# MCU_Module_V1.net
KiCad netlist of a schematic drawn in EAGLE
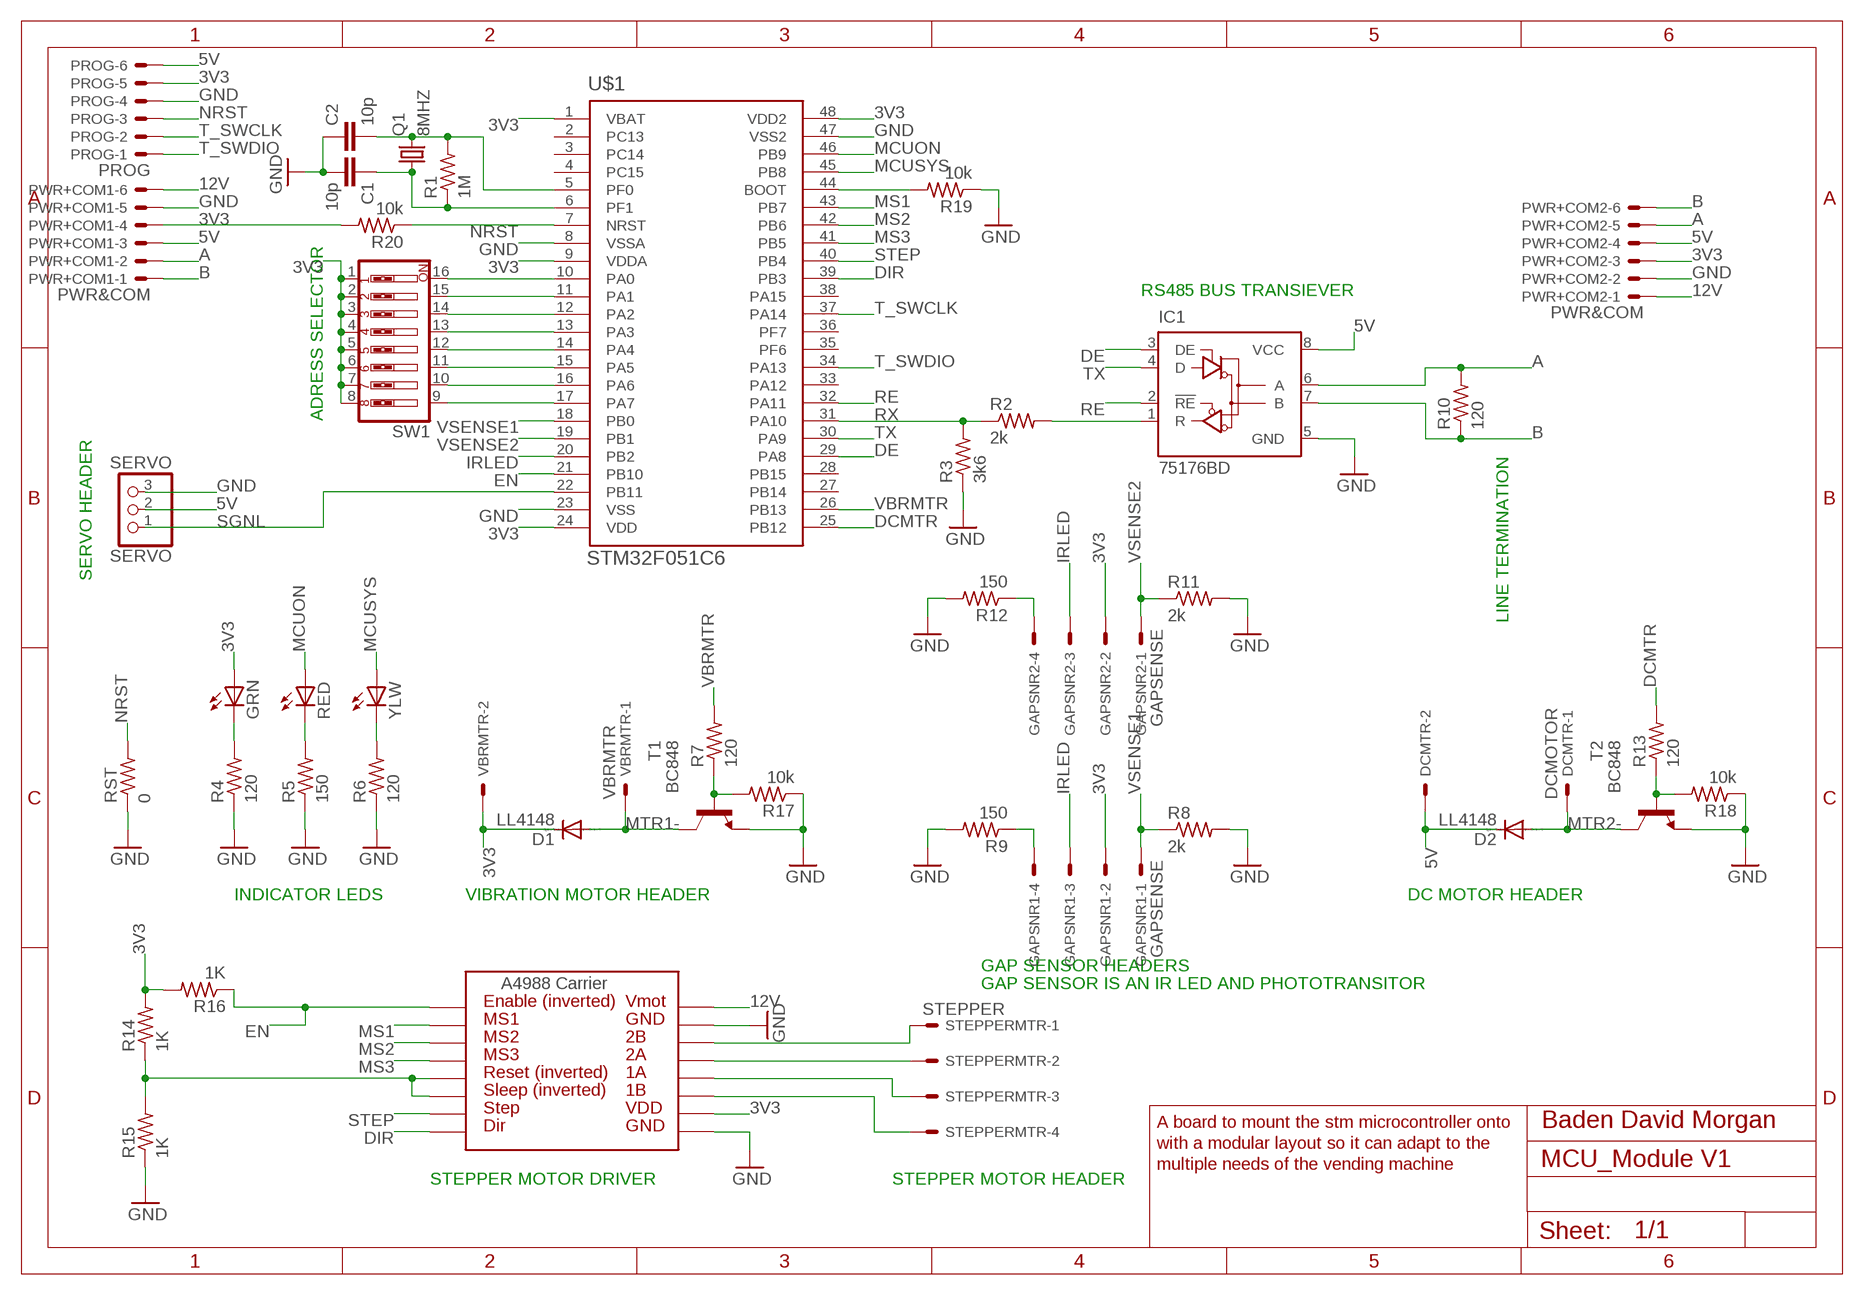
[diagram p0: schematic, sheet 1]

(export (version "E")
  (design (tool "Eeschema 10.0.6"))
  (components
    (comp (ref "C1")
      (value "10p")
      (footprint "eagle-import:C0805")
      (libsource (lib "eagle-import") (part "C-EUC0805"))
    )
    (comp (ref "C2")
      (value "10p")
      (footprint "eagle-import:C0805")
      (libsource (lib "eagle-import") (part "C-EUC0805"))
    )
    (comp (ref "D1")
      (value "LL4148")
      (footprint "eagle-import:SOD80C")
      (libsource (lib "eagle-import") (part "PMLL4150"))
    )
    (comp (ref "D2")
      (value "LL4148")
      (footprint "eagle-import:SOD80C")
      (libsource (lib "eagle-import") (part "PMLL4150"))
    )
    (comp (ref "DCMTR")
      (value "DCMOTOR")
      (footprint "eagle-import:6410-02")
      (libsource (lib "eagle-import") (part "22-?-0227-2021"))
    )
    (comp (ref "GAPSNR1")
      (value "GAPSENSE")
      (footprint "eagle-import:6410-04")
      (libsource (lib "eagle-import") (part "22-?-0427-2041"))
    )
    (comp (ref "GAPSNR2")
      (value "GAPSENSE")
      (footprint "eagle-import:6410-04")
      (libsource (lib "eagle-import") (part "22-?-0427-2041"))
    )
    (comp (ref "GRN")
      (value "LEDSML1206")
      (footprint "eagle-import:SML1206")
      (libsource (lib "eagle-import") (part "LEDSML1206"))
    )
    (comp (ref "IC1")
      (value "75176BD")
      (footprint "eagle-import:D_R-PDSO-G8")
      (libsource (lib "eagle-import") (part "75176AD"))
    )
    (comp (ref "PROG")
      (value "PROG")
      (footprint "eagle-import:6410-06")
      (libsource (lib "eagle-import") (part "22-?-0627-2061"))
    )
    (comp (ref "PWR+COM1")
      (value "PWR&COM")
      (footprint "eagle-import:7395-06")
      (libsource (lib "eagle-import") (part "22-?-0605-7068"))
    )
    (comp (ref "PWR+COM2")
      (value "PWR&COM")
      (footprint "eagle-import:7395-06")
      (libsource (lib "eagle-import") (part "22-?-0605-7068"))
    )
    (comp (ref "Q1")
      (value "8MHZ")
      (footprint "eagle-import:SM49")
      (libsource (lib "eagle-import") (part "CRYSTALSM49"))
    )
    (comp (ref "R1")
      (value "1M")
      (footprint "eagle-import:R0805")
      (libsource (lib "eagle-import") (part "R-US_R0805"))
    )
    (comp (ref "R2")
      (value "2k")
      (footprint "eagle-import:R0805")
      (libsource (lib "eagle-import") (part "resistor_R-US_R0805"))
    )
    (comp (ref "R3")
      (value "3k6")
      (footprint "eagle-import:R0805")
      (libsource (lib "eagle-import") (part "resistor_R-US_R0805"))
    )
    (comp (ref "R4")
      (value "120")
      (footprint "eagle-import:R0805")
      (libsource (lib "eagle-import") (part "R-US_R0805"))
    )
    (comp (ref "R5")
      (value "150")
      (footprint "eagle-import:R0805")
      (libsource (lib "eagle-import") (part "R-US_R0805"))
    )
    (comp (ref "R6")
      (value "120")
      (footprint "eagle-import:R0805")
      (libsource (lib "eagle-import") (part "R-US_R0805"))
    )
    (comp (ref "R7")
      (value "120")
      (footprint "eagle-import:R0805")
      (libsource (lib "eagle-import") (part "R-US_R0805"))
    )
    (comp (ref "R8")
      (value "2k")
      (footprint "eagle-import:R0805")
      (libsource (lib "eagle-import") (part "resistor_R-US_R0805"))
    )
    (comp (ref "R9")
      (value "150")
      (footprint "eagle-import:R0805")
      (libsource (lib "eagle-import") (part "R-US_R0805"))
    )
    (comp (ref "R10")
      (value "120")
      (footprint "eagle-import:R0805")
      (libsource (lib "eagle-import") (part "resistor_R-US_R0805"))
    )
    (comp (ref "R11")
      (value "2k")
      (footprint "eagle-import:R0805")
      (libsource (lib "eagle-import") (part "resistor_R-US_R0805"))
    )
    (comp (ref "R12")
      (value "150")
      (footprint "eagle-import:R0805")
      (libsource (lib "eagle-import") (part "R-US_R0805"))
    )
    (comp (ref "R13")
      (value "120")
      (footprint "eagle-import:R0805")
      (libsource (lib "eagle-import") (part "R-US_R0805"))
    )
    (comp (ref "R14")
      (value "1K")
      (footprint "eagle-import:R0805")
      (libsource (lib "eagle-import") (part "R-US_R0805"))
    )
    (comp (ref "R15")
      (value "1K")
      (footprint "eagle-import:R0805")
      (libsource (lib "eagle-import") (part "R-US_R0805"))
    )
    (comp (ref "R16")
      (value "1K")
      (footprint "eagle-import:R0805")
      (libsource (lib "eagle-import") (part "R-US_R0805"))
    )
    (comp (ref "R17")
      (value "10k")
      (footprint "eagle-import:R0805")
      (libsource (lib "eagle-import") (part "R-US_R0805"))
    )
    (comp (ref "R18")
      (value "10k")
      (footprint "eagle-import:R0805")
      (libsource (lib "eagle-import") (part "R-US_R0805"))
    )
    (comp (ref "R19")
      (value "10k")
      (footprint "eagle-import:R0805")
      (libsource (lib "eagle-import") (part "R-US_R0805"))
    )
    (comp (ref "R20")
      (value "10k")
      (footprint "eagle-import:R0805")
      (libsource (lib "eagle-import") (part "R-US_R0805"))
    )
    (comp (ref "RED")
      (value "LEDSML1206")
      (footprint "eagle-import:SML1206")
      (libsource (lib "eagle-import") (part "LEDSML1206"))
    )
    (comp (ref "RST")
      (value "0")
      (footprint "eagle-import:R0805")
      (libsource (lib "eagle-import") (part "R-US_R0805"))
    )
    (comp (ref "SERVO")
      (value "SERVO")
      (footprint "eagle-import:1X03")
      (libsource (lib "eagle-import") (part "PINHD-1X3"))
    )
    (comp (ref "STEPPERMTR")
      (value "STEPPER")
      (footprint "eagle-import:6410-04")
      (libsource (lib "eagle-import") (part "22-?-0427-2041"))
    )
    (comp (ref "SW1")
      (value "SW_DIP-8")
      (footprint "eagle-import:EDG-08")
      (libsource (lib "eagle-import") (part "SW_DIP-8"))
    )
    (comp (ref "T1")
      (value "BC848")
      (footprint "eagle-import:SOT23")
      (libsource (lib "eagle-import") (part "BC848"))
    )
    (comp (ref "T2")
      (value "BC848")
      (footprint "eagle-import:SOT23")
      (libsource (lib "eagle-import") (part "BC848"))
    )
    (comp (ref "U$1")
      (value "STM32F051C6")
      (footprint "eagle-import:QFP50P900X900X160-48N")
      (libsource (lib "eagle-import") (part "STM32F051C6"))
    )
    (comp (ref "U$2")
      (value "A4983CARRIER")
      (footprint "eagle-import:A4988BREAKOUT")
      (libsource (lib "eagle-import") (part "A4983CARRIER"))
    )
    (comp (ref "VBRMTR")
      (value "VBRMTR")
      (footprint "eagle-import:6410-02")
      (libsource (lib "eagle-import") (part "22-?-0227-2021"))
    )
    (comp (ref "YLW")
      (value "LEDSML1206")
      (footprint "eagle-import:SML1206")
      (libsource (lib "eagle-import") (part "LEDSML1206"))
    )
  )
  (nets
    (net (code "1") (name "/3V3") (class "Default")
      (node (ref "D1") (pin "C") (pinfunction "C_C") (pintype "passive"))
      (node (ref "GAPSNR1") (pin "2") (pinfunction "S_2") (pintype "passive"))
      (node (ref "GAPSNR2") (pin "2") (pinfunction "S_2") (pintype "passive"))
      (node (ref "GRN") (pin "A") (pinfunction "A_A") (pintype "passive"))
      (node (ref "PROG") (pin "5") (pinfunction "S_5") (pintype "passive"))
      (node (ref "PWR+COM1") (pin "4") (pinfunction "S_4") (pintype "passive"))
      (node (ref "PWR+COM2") (pin "3") (pinfunction "S_3") (pintype "passive"))
      (node (ref "R14") (pin "2") (pinfunction "2_2") (pintype "passive"))
      (node (ref "R16") (pin "2") (pinfunction "2_2") (pintype "passive"))
      (node (ref "R20") (pin "2") (pinfunction "2_2") (pintype "passive"))
      (node (ref "SW1") (pin "1") (pinfunction "1_1") (pintype "passive"))
      (node (ref "SW1") (pin "2") (pinfunction "2_2") (pintype "passive"))
      (node (ref "SW1") (pin "3") (pinfunction "3_3") (pintype "passive"))
      (node (ref "SW1") (pin "4") (pinfunction "4_4") (pintype "passive"))
      (node (ref "SW1") (pin "5") (pinfunction "5_5") (pintype "passive"))
      (node (ref "SW1") (pin "6") (pinfunction "6_6") (pintype "passive"))
      (node (ref "SW1") (pin "7") (pinfunction "7_7") (pintype "passive"))
      (node (ref "SW1") (pin "8") (pinfunction "8_8") (pintype "passive"))
      (node (ref "U$1") (pin "1") (pinfunction "VBAT_1") (pintype "bidirectional"))
      (node (ref "U$1") (pin "24") (pinfunction "VDD_24") (pintype "bidirectional"))
      (node (ref "U$1") (pin "48") (pinfunction "VDD2_48") (pintype "bidirectional"))
      (node (ref "U$1") (pin "9") (pinfunction "VDDA_9") (pintype "bidirectional"))
      (node (ref "U$2") (pin "VDD") (pinfunction "VDD_VDD") (pintype "power_in"))
      (node (ref "VBRMTR") (pin "2") (pinfunction "S_2") (pintype "passive"))
    )
    (net (code "2") (name "/5V") (class "Default")
      (node (ref "D2") (pin "C") (pinfunction "C_C") (pintype "passive"))
      (node (ref "DCMTR") (pin "2") (pinfunction "S_2") (pintype "passive"))
      (node (ref "IC1") (pin "8") (pinfunction "VCC_8") (pintype "power_in"))
      (node (ref "PROG") (pin "6") (pinfunction "S_6") (pintype "passive"))
      (node (ref "PWR+COM1") (pin "3") (pinfunction "S_3") (pintype "passive"))
      (node (ref "PWR+COM2") (pin "4") (pinfunction "S_4") (pintype "passive"))
      (node (ref "SERVO") (pin "2") (pinfunction "2_2") (pintype "passive"))
    )
    (net (code "3") (name "/12V") (class "Default")
      (node (ref "PWR+COM1") (pin "6") (pinfunction "S_6") (pintype "passive"))
      (node (ref "PWR+COM2") (pin "1") (pinfunction "S_1") (pintype "passive"))
      (node (ref "U$2") (pin "VMOT") (pinfunction "VMOT_VMOT") (pintype "power_in"))
    )
    (net (code "4") (name "/A") (class "Default")
      (node (ref "IC1") (pin "6") (pinfunction "A_6") (pintype "output"))
      (node (ref "PWR+COM1") (pin "2") (pinfunction "S_2") (pintype "passive"))
      (node (ref "PWR+COM2") (pin "5") (pinfunction "S_5") (pintype "passive"))
      (node (ref "R10") (pin "2") (pinfunction "2_2") (pintype "passive"))
    )
    (net (code "5") (name "/B") (class "Default")
      (node (ref "IC1") (pin "7") (pinfunction "B_7") (pintype "output"))
      (node (ref "PWR+COM1") (pin "1") (pinfunction "S_1") (pintype "passive"))
      (node (ref "PWR+COM2") (pin "6") (pinfunction "S_6") (pintype "passive"))
      (node (ref "R10") (pin "1") (pinfunction "1_1") (pintype "passive"))
    )
    (net (code "6") (name "/DCMTR") (class "Default")
      (node (ref "R13") (pin "2") (pinfunction "2_2") (pintype "passive"))
      (node (ref "U$1") (pin "25") (pinfunction "PB12_25") (pintype "bidirectional"))
    )
    (net (code "7") (name "/DE") (class "Default")
      (node (ref "IC1") (pin "3") (pinfunction "DE_3") (pintype "input"))
      (node (ref "U$1") (pin "29") (pinfunction "PA8_29") (pintype "bidirectional"))
    )
    (net (code "8") (name "/DIR") (class "Default")
      (node (ref "U$1") (pin "39") (pinfunction "PB3_39") (pintype "bidirectional"))
      (node (ref "U$2") (pin "DIR") (pinfunction "DIR_DIR") (pintype "input"))
    )
    (net (code "9") (name "/EN") (class "Default")
      (node (ref "R16") (pin "1") (pinfunction "1_1") (pintype "passive"))
      (node (ref "U$1") (pin "21") (pinfunction "PB10_21") (pintype "bidirectional"))
      (node (ref "U$2") (pin "EN") (pinfunction "EN_EN") (pintype "input"))
    )
    (net (code "10") (name "/IRLED") (class "Default")
      (node (ref "GAPSNR1") (pin "3") (pinfunction "S_3") (pintype "passive"))
      (node (ref "GAPSNR2") (pin "3") (pinfunction "S_3") (pintype "passive"))
      (node (ref "U$1") (pin "20") (pinfunction "PB2_20") (pintype "bidirectional"))
    )
    (net (code "11") (name "/MCUON") (class "Default")
      (node (ref "RED") (pin "A") (pinfunction "A_A") (pintype "passive"))
      (node (ref "U$1") (pin "46") (pinfunction "PB9_46") (pintype "bidirectional"))
    )
    (net (code "12") (name "/MCUSYS") (class "Default")
      (node (ref "U$1") (pin "45") (pinfunction "PB8_45") (pintype "bidirectional"))
      (node (ref "YLW") (pin "A") (pinfunction "A_A") (pintype "passive"))
    )
    (net (code "13") (name "/MS1") (class "Default")
      (node (ref "U$1") (pin "43") (pinfunction "PB7_43") (pintype "bidirectional"))
      (node (ref "U$2") (pin "MS1") (pinfunction "MS1_MS1") (pintype "input"))
    )
    (net (code "14") (name "/MS2") (class "Default")
      (node (ref "U$1") (pin "42") (pinfunction "PB6_42") (pintype "bidirectional"))
      (node (ref "U$2") (pin "MS2") (pinfunction "MS2_MS2") (pintype "input"))
    )
    (net (code "15") (name "/MS3") (class "Default")
      (node (ref "U$1") (pin "41") (pinfunction "PB5_41") (pintype "bidirectional"))
      (node (ref "U$2") (pin "MS3") (pinfunction "MS3_MS3") (pintype "input"))
    )
    (net (code "16") (name "/MTR1-") (class "Default")
      (node (ref "D1") (pin "A") (pinfunction "A_A") (pintype "passive"))
      (node (ref "T1") (pin "3") (pinfunction "C_3") (pintype "passive"))
      (node (ref "VBRMTR") (pin "1") (pinfunction "S_1") (pintype "passive"))
    )
    (net (code "17") (name "/MTR2-") (class "Default")
      (node (ref "D2") (pin "A") (pinfunction "A_A") (pintype "passive"))
      (node (ref "DCMTR") (pin "1") (pinfunction "S_1") (pintype "passive"))
      (node (ref "T2") (pin "3") (pinfunction "C_3") (pintype "passive"))
    )
    (net (code "18") (name "/NRST") (class "Default")
      (node (ref "PROG") (pin "3") (pinfunction "S_3") (pintype "passive"))
      (node (ref "R20") (pin "1") (pinfunction "1_1") (pintype "passive"))
      (node (ref "RST") (pin "2") (pinfunction "2_2") (pintype "passive"))
      (node (ref "U$1") (pin "7") (pinfunction "NRST_7") (pintype "bidirectional"))
    )
    (net (code "19") (name "/RE") (class "Default")
      (node (ref "IC1") (pin "2") (pinfunction "~{RE}_2") (pintype "input"))
      (node (ref "U$1") (pin "32") (pinfunction "PA11_32") (pintype "bidirectional"))
    )
    (net (code "20") (name "/RX") (class "Default")
      (node (ref "R2") (pin "1") (pinfunction "1_1") (pintype "passive"))
      (node (ref "R3") (pin "2") (pinfunction "2_2") (pintype "passive"))
      (node (ref "U$1") (pin "31") (pinfunction "PA10_31") (pintype "bidirectional"))
    )
    (net (code "21") (name "/SGNL") (class "Default")
      (node (ref "SERVO") (pin "1") (pinfunction "1_1") (pintype "passive"))
      (node (ref "U$1") (pin "22") (pinfunction "PB11_22") (pintype "bidirectional"))
    )
    (net (code "22") (name "/STEP") (class "Default")
      (node (ref "U$1") (pin "40") (pinfunction "PB4_40") (pintype "bidirectional"))
      (node (ref "U$2") (pin "STEP") (pinfunction "STEP_STEP") (pintype "input"))
    )
    (net (code "23") (name "/TX") (class "Default")
      (node (ref "IC1") (pin "4") (pinfunction "D_4") (pintype "input"))
      (node (ref "U$1") (pin "30") (pinfunction "PA9_30") (pintype "bidirectional"))
    )
    (net (code "24") (name "/T_SWCLK") (class "Default")
      (node (ref "PROG") (pin "2") (pinfunction "S_2") (pintype "passive"))
      (node (ref "U$1") (pin "37") (pinfunction "PA14_37") (pintype "bidirectional"))
    )
    (net (code "25") (name "/T_SWDIO") (class "Default")
      (node (ref "PROG") (pin "1") (pinfunction "S_1") (pintype "passive"))
      (node (ref "U$1") (pin "34") (pinfunction "PA13_34") (pintype "bidirectional"))
    )
    (net (code "26") (name "/VBRMTR") (class "Default")
      (node (ref "R7") (pin "2") (pinfunction "2_2") (pintype "passive"))
      (node (ref "U$1") (pin "26") (pinfunction "PB13_26") (pintype "bidirectional"))
    )
    (net (code "27") (name "/VSENSE1") (class "Default")
      (node (ref "GAPSNR1") (pin "1") (pinfunction "S_1") (pintype "passive"))
      (node (ref "R8") (pin "1") (pinfunction "1_1") (pintype "passive"))
      (node (ref "U$1") (pin "18") (pinfunction "PB0_18") (pintype "bidirectional"))
    )
    (net (code "28") (name "/VSENSE2") (class "Default")
      (node (ref "GAPSNR2") (pin "1") (pinfunction "S_1") (pintype "passive"))
      (node (ref "R11") (pin "1") (pinfunction "1_1") (pintype "passive"))
      (node (ref "U$1") (pin "19") (pinfunction "PB1_19") (pintype "bidirectional"))
    )
    (net (code "29") (name "GND") (class "Default")
      (node (ref "C1") (pin "2") (pinfunction "2_2") (pintype "passive"))
      (node (ref "C2") (pin "1") (pinfunction "1_1") (pintype "passive"))
      (node (ref "IC1") (pin "5") (pinfunction "GND_5") (pintype "power_in"))
      (node (ref "PROG") (pin "4") (pinfunction "S_4") (pintype "passive"))
      (node (ref "PWR+COM1") (pin "5") (pinfunction "S_5") (pintype "passive"))
      (node (ref "PWR+COM2") (pin "2") (pinfunction "S_2") (pintype "passive"))
      (node (ref "R11") (pin "2") (pinfunction "2_2") (pintype "passive"))
      (node (ref "R12") (pin "2") (pinfunction "2_2") (pintype "passive"))
      (node (ref "R15") (pin "1") (pinfunction "1_1") (pintype "passive"))
      (node (ref "R17") (pin "1") (pinfunction "1_1") (pintype "passive"))
      (node (ref "R18") (pin "1") (pinfunction "1_1") (pintype "passive"))
      (node (ref "R19") (pin "1") (pinfunction "1_1") (pintype "passive"))
      (node (ref "R3") (pin "1") (pinfunction "1_1") (pintype "passive"))
      (node (ref "R4") (pin "1") (pinfunction "1_1") (pintype "passive"))
      (node (ref "R5") (pin "1") (pinfunction "1_1") (pintype "passive"))
      (node (ref "R6") (pin "1") (pinfunction "1_1") (pintype "passive"))
      (node (ref "R8") (pin "2") (pinfunction "2_2") (pintype "passive"))
      (node (ref "R9") (pin "2") (pinfunction "2_2") (pintype "passive"))
      (node (ref "RST") (pin "1") (pinfunction "1_1") (pintype "passive"))
      (node (ref "SERVO") (pin "3") (pinfunction "3_3") (pintype "passive"))
      (node (ref "T1") (pin "2") (pinfunction "E_2") (pintype "passive"))
      (node (ref "T2") (pin "2") (pinfunction "E_2") (pintype "passive"))
      (node (ref "U$1") (pin "23") (pinfunction "VSS_23") (pintype "bidirectional"))
      (node (ref "U$1") (pin "47") (pinfunction "VSS2_47") (pintype "bidirectional"))
      (node (ref "U$1") (pin "8") (pinfunction "VSSA_8") (pintype "bidirectional"))
      (node (ref "U$2") (pin "GND") (pinfunction "GND_GND") (pintype "power_in"))
      (node (ref "U$2") (pin "GND@0") (pinfunction "GND_GND@0") (pintype "power_in"))
    )
    (net (code "30") (name "Net-(GAPSNR1D-S)") (class "Default")
      (node (ref "GAPSNR1") (pin "4") (pinfunction "S_4") (pintype "passive"))
      (node (ref "R9") (pin "1") (pinfunction "1_1") (pintype "passive"))
    )
    (net (code "31") (name "Net-(GAPSNR2D-S)") (class "Default")
      (node (ref "GAPSNR2") (pin "4") (pinfunction "S_4") (pintype "passive"))
      (node (ref "R12") (pin "1") (pinfunction "1_1") (pintype "passive"))
    )
    (net (code "32") (name "Net-(GRN-PadC)") (class "Default")
      (node (ref "GRN") (pin "C") (pinfunction "C_C") (pintype "passive"))
      (node (ref "R4") (pin "2") (pinfunction "2_2") (pintype "passive"))
    )
    (net (code "33") (name "Net-(IC1-R)") (class "Default")
      (node (ref "IC1") (pin "1") (pinfunction "R_1") (pintype "input"))
      (node (ref "R2") (pin "2") (pinfunction "2_2") (pintype "passive"))
    )
    (net (code "34") (name "Net-(R5-Pad2)") (class "Default")
      (node (ref "R5") (pin "2") (pinfunction "2_2") (pintype "passive"))
      (node (ref "RED") (pin "C") (pinfunction "C_C") (pintype "passive"))
    )
    (net (code "35") (name "Net-(R6-Pad2)") (class "Default")
      (node (ref "R6") (pin "2") (pinfunction "2_2") (pintype "passive"))
      (node (ref "YLW") (pin "C") (pinfunction "C_C") (pintype "passive"))
    )
    (net (code "36") (name "Net-(STEPPERMTRA-S)") (class "Default")
      (node (ref "STEPPERMTR") (pin "1") (pinfunction "S_1") (pintype "passive"))
      (node (ref "U$2") (pin "2B") (pinfunction "2B_2B") (pintype "output"))
    )
    (net (code "37") (name "Net-(STEPPERMTRB-S)") (class "Default")
      (node (ref "STEPPERMTR") (pin "2") (pinfunction "S_2") (pintype "passive"))
      (node (ref "U$2") (pin "2A") (pinfunction "2A_2A") (pintype "output"))
    )
    (net (code "38") (name "Net-(STEPPERMTRC-S)") (class "Default")
      (node (ref "STEPPERMTR") (pin "3") (pinfunction "S_3") (pintype "passive"))
      (node (ref "U$2") (pin "1A") (pinfunction "1A_1A") (pintype "output"))
    )
    (net (code "39") (name "Net-(STEPPERMTRD-S)") (class "Default")
      (node (ref "STEPPERMTR") (pin "4") (pinfunction "S_4") (pintype "passive"))
      (node (ref "U$2") (pin "1B") (pinfunction "1B_1B") (pintype "output"))
    )
    (net (code "40") (name "Net-(T1-B)") (class "Default")
      (node (ref "R17") (pin "2") (pinfunction "2_2") (pintype "passive"))
      (node (ref "R7") (pin "1") (pinfunction "1_1") (pintype "passive"))
      (node (ref "T1") (pin "1") (pinfunction "B_1") (pintype "passive"))
    )
    (net (code "41") (name "Net-(T2-B)") (class "Default")
      (node (ref "R13") (pin "1") (pinfunction "1_1") (pintype "passive"))
      (node (ref "R18") (pin "2") (pinfunction "2_2") (pintype "passive"))
      (node (ref "T2") (pin "1") (pinfunction "B_1") (pintype "passive"))
    )
    (net (code "42") (name "Net-(U$1-BOOT)") (class "Default")
      (node (ref "R19") (pin "2") (pinfunction "2_2") (pintype "passive"))
      (node (ref "U$1") (pin "44") (pinfunction "BOOT_44") (pintype "bidirectional"))
    )
    (net (code "43") (name "Net-(U$1-PA0)") (class "Default")
      (node (ref "SW1") (pin "16") (pinfunction "16_16") (pintype "passive"))
      (node (ref "U$1") (pin "10") (pinfunction "PA0_10") (pintype "bidirectional"))
    )
    (net (code "44") (name "Net-(U$1-PA1)") (class "Default")
      (node (ref "SW1") (pin "15") (pinfunction "15_15") (pintype "passive"))
      (node (ref "U$1") (pin "11") (pinfunction "PA1_11") (pintype "bidirectional"))
    )
    (net (code "45") (name "Net-(U$1-PA2)") (class "Default")
      (node (ref "SW1") (pin "14") (pinfunction "14_14") (pintype "passive"))
      (node (ref "U$1") (pin "12") (pinfunction "PA2_12") (pintype "bidirectional"))
    )
    (net (code "46") (name "Net-(U$1-PA3)") (class "Default")
      (node (ref "SW1") (pin "13") (pinfunction "13_13") (pintype "passive"))
      (node (ref "U$1") (pin "13") (pinfunction "PA3_13") (pintype "bidirectional"))
    )
    (net (code "47") (name "Net-(U$1-PA4)") (class "Default")
      (node (ref "SW1") (pin "12") (pinfunction "12_12") (pintype "passive"))
      (node (ref "U$1") (pin "14") (pinfunction "PA4_14") (pintype "bidirectional"))
    )
    (net (code "48") (name "Net-(U$1-PA5)") (class "Default")
      (node (ref "SW1") (pin "11") (pinfunction "11_11") (pintype "passive"))
      (node (ref "U$1") (pin "15") (pinfunction "PA5_15") (pintype "bidirectional"))
    )
    (net (code "49") (name "Net-(U$1-PA6)") (class "Default")
      (node (ref "SW1") (pin "10") (pinfunction "10_10") (pintype "passive"))
      (node (ref "U$1") (pin "16") (pinfunction "PA6_16") (pintype "bidirectional"))
    )
    (net (code "50") (name "Net-(U$1-PA7)") (class "Default")
      (node (ref "SW1") (pin "9") (pinfunction "9_9") (pintype "passive"))
      (node (ref "U$1") (pin "17") (pinfunction "PA7_17") (pintype "bidirectional"))
    )
    (net (code "51") (name "Net-(U$1-PF0)") (class "Default")
      (node (ref "C2") (pin "2") (pinfunction "2_2") (pintype "passive"))
      (node (ref "Q1") (pin "2") (pinfunction "2_2") (pintype "passive"))
      (node (ref "R1") (pin "2") (pinfunction "2_2") (pintype "passive"))
      (node (ref "U$1") (pin "5") (pinfunction "PF0_5") (pintype "bidirectional"))
    )
    (net (code "52") (name "Net-(U$1-PF1)") (class "Default")
      (node (ref "C1") (pin "1") (pinfunction "1_1") (pintype "passive"))
      (node (ref "Q1") (pin "1") (pinfunction "1_1") (pintype "passive"))
      (node (ref "R1") (pin "1") (pinfunction "1_1") (pintype "passive"))
      (node (ref "U$1") (pin "6") (pinfunction "PF1_6") (pintype "bidirectional"))
    )
    (net (code "53") (name "Net-(U$2-SLEEP)") (class "Default")
      (node (ref "R14") (pin "1") (pinfunction "1_1") (pintype "passive"))
      (node (ref "R15") (pin "2") (pinfunction "2_2") (pintype "passive"))
      (node (ref "U$2") (pin "RST") (pinfunction "RST_RST") (pintype "input"))
      (node (ref "U$2") (pin "SLP") (pinfunction "SLEEP_SLP") (pintype "input"))
    )
    (net (code "54") (name "unconnected-(U$1-PA12-Pad33)") (class "Default")
      (node (ref "U$1") (pin "33") (pinfunction "PA12_33") (pintype "bidirectional"))
    )
    (net (code "55") (name "unconnected-(U$1-PA15-Pad38)") (class "Default")
      (node (ref "U$1") (pin "38") (pinfunction "PA15_38") (pintype "bidirectional"))
    )
    (net (code "56") (name "unconnected-(U$1-PB14-Pad27)") (class "Default")
      (node (ref "U$1") (pin "27") (pinfunction "PB14_27") (pintype "bidirectional"))
    )
    (net (code "57") (name "unconnected-(U$1-PB15-Pad28)") (class "Default")
      (node (ref "U$1") (pin "28") (pinfunction "PB15_28") (pintype "bidirectional"))
    )
    (net (code "58") (name "unconnected-(U$1-PC13-Pad2)") (class "Default")
      (node (ref "U$1") (pin "2") (pinfunction "PC13_2") (pintype "bidirectional"))
    )
    (net (code "59") (name "unconnected-(U$1-PC14-Pad3)") (class "Default")
      (node (ref "U$1") (pin "3") (pinfunction "PC14_3") (pintype "bidirectional"))
    )
    (net (code "60") (name "unconnected-(U$1-PC15-Pad4)") (class "Default")
      (node (ref "U$1") (pin "4") (pinfunction "PC15_4") (pintype "bidirectional"))
    )
    (net (code "61") (name "unconnected-(U$1-PF6-Pad35)") (class "Default")
      (node (ref "U$1") (pin "35") (pinfunction "PF6_35") (pintype "bidirectional"))
    )
    (net (code "62") (name "unconnected-(U$1-PF7-Pad36)") (class "Default")
      (node (ref "U$1") (pin "36") (pinfunction "PF7_36") (pintype "bidirectional"))
    )
  )
)
